# SCH.net
KiCad netlist of a schematic drawn in Altium Designer
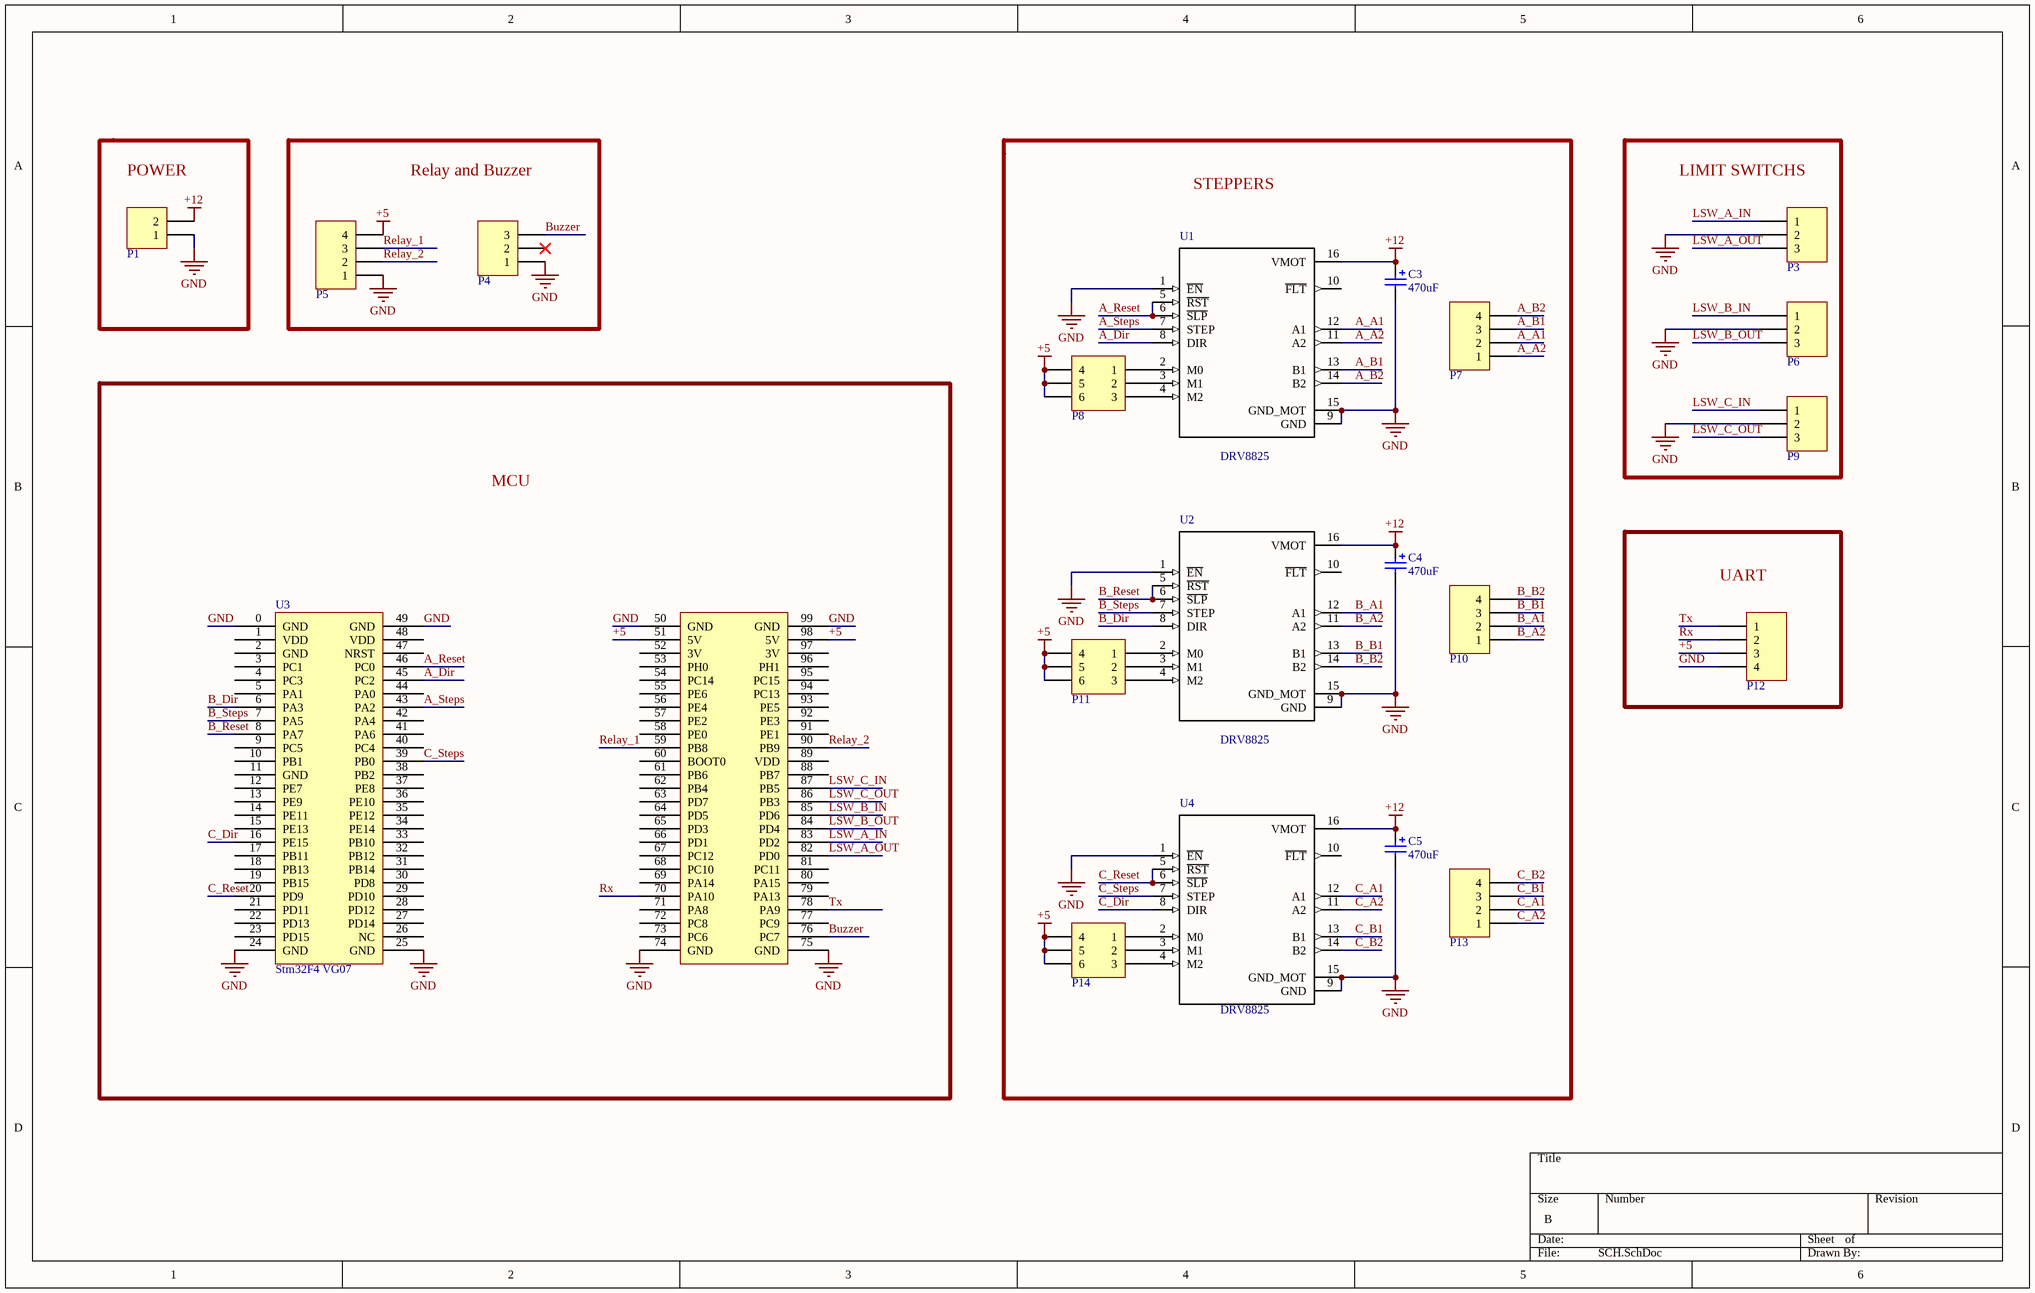
[diagram p0: SCH.SchDoc]

(export (version "E")
  (design (tool "Eeschema 10.0.6"))
  (components
    (comp (ref "C3")
      (value "470uF")
      (footprint "CP1.5/3.4")
      (description "Polarized Capacitor (Radial)")
      (fields (field (name "Comment") "Cap Pol"))
      (libsource (lib "PIF_Library") (part "Cap Pol"))
    )
    (comp (ref "C4")
      (value "470uF")
      (footprint "CP1.5/3.4")
      (description "Polarized Capacitor (Radial)")
      (fields (field (name "Comment") "Cap Pol"))
      (libsource (lib "PIF_Library") (part "Cap Pol"))
    )
    (comp (ref "C5")
      (value "470uF")
      (footprint "CP1.5/3.4")
      (description "Polarized Capacitor (Radial)")
      (fields (field (name "Comment") "Cap Pol"))
      (libsource (lib "PIF_Library") (part "Cap Pol"))
    )
    (comp (ref "P1")
      (value "Domino 2")
      (footprint "DOMINO 2- 5mm")
      (description "Domino, 2-Pin")
      (fields (field (name "PUBLISHER") "Altium Limited"))
      (libsource (lib "PIF_Library") (part "Domino 2"))
    )
    (comp (ref "P3")
      (value "Header 3")
      (footprint "JP3")
      (description "Header, 3-Pin")
      (fields (field (name "PUBLISHER") "Altium Limited"))
      (libsource (lib "PIF_Library") (part "Header 3"))
    )
    (comp (ref "P4")
      (value "Header 3")
      (footprint "JP3")
      (description "Header, 3-Pin")
      (fields (field (name "PUBLISHER") "Altium Limited"))
      (libsource (lib "") (part "Header 3_1"))
    )
    (comp (ref "P5")
      (value "Domino 4")
      (footprint "DOMINO 4 -5mm")
      (description "Domino 4-Pin")
      (fields (field (name "PUBLISHER") "Altium Limited"))
      (libsource (lib "PIF_Library") (part "Domino 4"))
    )
    (comp (ref "P6")
      (value "Header 3")
      (footprint "JP3")
      (description "Header, 3-Pin")
      (fields (field (name "PUBLISHER") "Altium Limited"))
      (libsource (lib "PIF_Library") (part "Header 3"))
    )
    (comp (ref "P7")
      (value "Header 4")
      (footprint "JP4")
      (description "Header, 4-Pin")
      (fields (field (name "PUBLISHER") "Altium Limited"))
      (libsource (lib "") (part "Header 4_1"))
    )
    (comp (ref "P8")
      (value "Header 3X2")
      (footprint "JP3x2")
      (description "Header, 3-Pin, Dual row")
      (fields (field (name "PUBLISHER") "Altium Limited"))
      (libsource (lib "PIF_Library") (part "Header 3X2"))
    )
    (comp (ref "P9")
      (value "Header 3")
      (footprint "JP3")
      (description "Header, 3-Pin")
      (fields (field (name "PUBLISHER") "Altium Limited"))
      (libsource (lib "PIF_Library") (part "Header 3"))
    )
    (comp (ref "P10")
      (value "Header 4")
      (footprint "JP4")
      (description "Header, 4-Pin")
      (fields (field (name "PUBLISHER") "Altium Limited"))
      (libsource (lib "") (part "Header 4_1"))
    )
    (comp (ref "P11")
      (value "Header 3X2")
      (footprint "JP3x2")
      (description "Header, 3-Pin, Dual row")
      (fields (field (name "PUBLISHER") "Altium Limited"))
      (libsource (lib "PIF_Library") (part "Header 3X2"))
    )
    (comp (ref "P12")
      (value "Header 4")
      (footprint "JP4")
      (description "Header, 4-Pin")
      (fields (field (name "PUBLISHER") "Altium Limited"))
      (libsource (lib "PIF_Library") (part "Header 4"))
    )
    (comp (ref "P13")
      (value "Header 4")
      (footprint "JP4")
      (description "Header, 4-Pin")
      (fields (field (name "PUBLISHER") "Altium Limited"))
      (libsource (lib "") (part "Header 4_1"))
    )
    (comp (ref "P14")
      (value "Header 3X2")
      (footprint "JP3x2")
      (description "Header, 3-Pin, Dual row")
      (fields (field (name "PUBLISHER") "Altium Limited"))
      (libsource (lib "PIF_Library") (part "Header 3X2"))
    )
    (comp (ref "U1")
      (value "DRV8825")
      (footprint "*IC_DRV8825_STEPPER_MOTOR_DRIVER_CARRIER")
      (description "DRV8825 Motor Controller/Driver Power Management Evaluation Board")
      (fields (field (name "MP") "DRV8825 STEPPER MOTOR DRIVER CARRIER") (field (name "MF") "Pololu"))
      (libsource (lib "DRV8825_STEPPER_MOTOR_DRIVER_CARRIER") (part "DRV8825_STEPPER_MOTOR_DRIVER_CARRIER"))
    )
    (comp (ref "U2")
      (value "DRV8825")
      (footprint "*IC_DRV8825_STEPPER_MOTOR_DRIVER_CARRIER")
      (description "DRV8825 Motor Controller/Driver Power Management Evaluation Board")
      (fields (field (name "MP") "DRV8825 STEPPER MOTOR DRIVER CARRIER") (field (name "MF") "Pololu"))
      (libsource (lib "DRV8825_STEPPER_MOTOR_DRIVER_CARRIER") (part "DRV8825_STEPPER_MOTOR_DRIVER_CARRIER"))
    )
    (comp (ref "U3")
      (value "Stm32F4 VG07")
      (footprint "stm32f4 hoan chinh")
      (libsource (lib "stm32f4 VG07 hoang loi") (part "STM32F4_VG07 Hoang Loi"))
    )
    (comp (ref "U4")
      (value "DRV8825")
      (footprint "*IC_DRV8825_STEPPER_MOTOR_DRIVER_CARRIER")
      (description "DRV8825 Motor Controller/Driver Power Management Evaluation Board")
      (fields (field (name "MP") "DRV8825 STEPPER MOTOR DRIVER CARRIER") (field (name "MF") "Pololu"))
      (libsource (lib "DRV8825_STEPPER_MOTOR_DRIVER_CARRIER") (part "DRV8825_STEPPER_MOTOR_DRIVER_CARRIER"))
    )
  )
  (nets
    (net (code "1") (name "+5") (class "Default")
      (node (ref "P11") (pin "4") (pinfunction "4_4") (pintype "passive"))
      (node (ref "P11") (pin "5") (pinfunction "5_5") (pintype "passive"))
      (node (ref "P11") (pin "6") (pinfunction "6_6") (pintype "passive"))
      (node (ref "P12") (pin "3") (pinfunction "3_3") (pintype "passive"))
      (node (ref "P14") (pin "4") (pinfunction "4_4") (pintype "passive"))
      (node (ref "P14") (pin "5") (pinfunction "5_5") (pintype "passive"))
      (node (ref "P14") (pin "6") (pinfunction "6_6") (pintype "passive"))
      (node (ref "P5") (pin "4") (pinfunction "4_4") (pintype "passive"))
      (node (ref "P8") (pin "4") (pinfunction "4_4") (pintype "passive"))
      (node (ref "P8") (pin "5") (pinfunction "5_5") (pintype "passive"))
      (node (ref "P8") (pin "6") (pinfunction "6_6") (pintype "passive"))
      (node (ref "U3") (pin "51") (pinfunction "5V_51") (pintype "passive"))
      (node (ref "U3") (pin "98") (pinfunction "5V_98") (pintype "passive"))
    )
    (net (code "2") (name "+12") (class "Default")
      (node (ref "C3") (pin "1") (pinfunction "1_1") (pintype "passive"))
      (node (ref "C4") (pin "1") (pinfunction "1_1") (pintype "passive"))
      (node (ref "C5") (pin "1") (pinfunction "1_1") (pintype "passive"))
      (node (ref "P1") (pin "2") (pinfunction "2_2") (pintype "passive"))
      (node (ref "U1") (pin "16") (pinfunction "VMOT_16") (pintype "power_in"))
      (node (ref "U2") (pin "16") (pinfunction "VMOT_16") (pintype "power_in"))
      (node (ref "U4") (pin "16") (pinfunction "VMOT_16") (pintype "power_in"))
    )
    (net (code "3") (name "/A_A1") (class "Default")
      (node (ref "P7") (pin "2") (pinfunction "2_2") (pintype "passive"))
      (node (ref "U1") (pin "12") (pinfunction "A1_12") (pintype "output"))
    )
    (net (code "4") (name "/A_A2") (class "Default")
      (node (ref "P7") (pin "1") (pinfunction "1_1") (pintype "passive"))
      (node (ref "U1") (pin "11") (pinfunction "A2_11") (pintype "output"))
    )
    (net (code "5") (name "/A_B1") (class "Default")
      (node (ref "P7") (pin "3") (pinfunction "3_3") (pintype "passive"))
      (node (ref "U1") (pin "13") (pinfunction "B1_13") (pintype "output"))
    )
    (net (code "6") (name "/A_B2") (class "Default")
      (node (ref "P7") (pin "4") (pinfunction "4_4") (pintype "passive"))
      (node (ref "U1") (pin "14") (pinfunction "B2_14") (pintype "output"))
    )
    (net (code "7") (name "/A_Dir") (class "Default")
      (node (ref "U1") (pin "8") (pinfunction "DIR_8") (pintype "input"))
      (node (ref "U3") (pin "45") (pinfunction "PC2_45") (pintype "passive"))
    )
    (net (code "8") (name "/A_Reset") (class "Default")
      (node (ref "U1") (pin "5") (pinfunction "~{RST}_5") (pintype "input"))
      (node (ref "U1") (pin "6") (pinfunction "~{SLP}_6") (pintype "input"))
      (node (ref "U3") (pin "46") (pinfunction "PC0_46") (pintype "passive"))
    )
    (net (code "9") (name "/A_Steps") (class "Default")
      (node (ref "U1") (pin "7") (pinfunction "STEP_7") (pintype "input"))
      (node (ref "U3") (pin "43") (pinfunction "PA2_43") (pintype "passive"))
    )
    (net (code "10") (name "/B_A1") (class "Default")
      (node (ref "P10") (pin "2") (pinfunction "2_2") (pintype "passive"))
      (node (ref "U2") (pin "12") (pinfunction "A1_12") (pintype "output"))
    )
    (net (code "11") (name "/B_A2") (class "Default")
      (node (ref "P10") (pin "1") (pinfunction "1_1") (pintype "passive"))
      (node (ref "U2") (pin "11") (pinfunction "A2_11") (pintype "output"))
    )
    (net (code "12") (name "/B_B1") (class "Default")
      (node (ref "P10") (pin "3") (pinfunction "3_3") (pintype "passive"))
      (node (ref "U2") (pin "13") (pinfunction "B1_13") (pintype "output"))
    )
    (net (code "13") (name "/B_B2") (class "Default")
      (node (ref "P10") (pin "4") (pinfunction "4_4") (pintype "passive"))
      (node (ref "U2") (pin "14") (pinfunction "B2_14") (pintype "output"))
    )
    (net (code "14") (name "/B_Dir") (class "Default")
      (node (ref "U2") (pin "8") (pinfunction "DIR_8") (pintype "input"))
      (node (ref "U3") (pin "6") (pinfunction "PA3_6") (pintype "passive"))
    )
    (net (code "15") (name "/B_Reset") (class "Default")
      (node (ref "U2") (pin "5") (pinfunction "~{RST}_5") (pintype "input"))
      (node (ref "U2") (pin "6") (pinfunction "~{SLP}_6") (pintype "input"))
      (node (ref "U3") (pin "8") (pinfunction "PA7_8") (pintype "passive"))
    )
    (net (code "16") (name "/B_Steps") (class "Default")
      (node (ref "U2") (pin "7") (pinfunction "STEP_7") (pintype "input"))
      (node (ref "U3") (pin "7") (pinfunction "PA5_7") (pintype "passive"))
    )
    (net (code "17") (name "/Buzzer") (class "Default")
      (node (ref "P4") (pin "3") (pinfunction "3_3") (pintype "passive"))
      (node (ref "U3") (pin "76") (pinfunction "PC7_76") (pintype "passive"))
    )
    (net (code "18") (name "/C_A1") (class "Default")
      (node (ref "P13") (pin "2") (pinfunction "2_2") (pintype "passive"))
      (node (ref "U4") (pin "12") (pinfunction "A1_12") (pintype "output"))
    )
    (net (code "19") (name "/C_A2") (class "Default")
      (node (ref "P13") (pin "1") (pinfunction "1_1") (pintype "passive"))
      (node (ref "U4") (pin "11") (pinfunction "A2_11") (pintype "output"))
    )
    (net (code "20") (name "/C_B1") (class "Default")
      (node (ref "P13") (pin "3") (pinfunction "3_3") (pintype "passive"))
      (node (ref "U4") (pin "13") (pinfunction "B1_13") (pintype "output"))
    )
    (net (code "21") (name "/C_B2") (class "Default")
      (node (ref "P13") (pin "4") (pinfunction "4_4") (pintype "passive"))
      (node (ref "U4") (pin "14") (pinfunction "B2_14") (pintype "output"))
    )
    (net (code "22") (name "/C_Dir") (class "Default")
      (node (ref "U3") (pin "16") (pinfunction "PE15_16") (pintype "passive"))
      (node (ref "U4") (pin "8") (pinfunction "DIR_8") (pintype "input"))
    )
    (net (code "23") (name "/C_Reset") (class "Default")
      (node (ref "U3") (pin "20") (pinfunction "PD9_20") (pintype "passive"))
      (node (ref "U4") (pin "5") (pinfunction "~{RST}_5") (pintype "input"))
      (node (ref "U4") (pin "6") (pinfunction "~{SLP}_6") (pintype "input"))
    )
    (net (code "24") (name "/C_Steps") (class "Default")
      (node (ref "U3") (pin "39") (pinfunction "PB0_39") (pintype "passive"))
      (node (ref "U4") (pin "7") (pinfunction "STEP_7") (pintype "input"))
    )
    (net (code "25") (name "/LSW_A_IN") (class "Default")
      (node (ref "P3") (pin "1") (pinfunction "1_1") (pintype "passive"))
      (node (ref "U3") (pin "83") (pinfunction "PD2_83") (pintype "passive"))
    )
    (net (code "26") (name "/LSW_A_OUT") (class "Default")
      (node (ref "P3") (pin "3") (pinfunction "3_3") (pintype "passive"))
      (node (ref "U3") (pin "82") (pinfunction "PD0_82") (pintype "passive"))
    )
    (net (code "27") (name "/LSW_B_IN") (class "Default")
      (node (ref "P6") (pin "1") (pinfunction "1_1") (pintype "passive"))
      (node (ref "U3") (pin "85") (pinfunction "PD6_85") (pintype "passive"))
    )
    (net (code "28") (name "/LSW_B_OUT") (class "Default")
      (node (ref "P6") (pin "3") (pinfunction "3_3") (pintype "passive"))
      (node (ref "U3") (pin "84") (pinfunction "PD4_84") (pintype "passive"))
    )
    (net (code "29") (name "/LSW_C_IN") (class "Default")
      (node (ref "P9") (pin "1") (pinfunction "1_1") (pintype "passive"))
      (node (ref "U3") (pin "87") (pinfunction "PB5_87") (pintype "passive"))
    )
    (net (code "30") (name "/LSW_C_OUT") (class "Default")
      (node (ref "P9") (pin "3") (pinfunction "3_3") (pintype "passive"))
      (node (ref "U3") (pin "86") (pinfunction "PB3_86") (pintype "passive"))
    )
    (net (code "31") (name "/Relay_1") (class "Default")
      (node (ref "P5") (pin "3") (pinfunction "3_3") (pintype "passive"))
      (node (ref "U3") (pin "59") (pinfunction "PB8_59") (pintype "passive"))
    )
    (net (code "32") (name "/Relay_2") (class "Default")
      (node (ref "P5") (pin "2") (pinfunction "2_2") (pintype "passive"))
      (node (ref "U3") (pin "90") (pinfunction "PB9_90") (pintype "passive"))
    )
    (net (code "33") (name "/Rx") (class "Default")
      (node (ref "P12") (pin "2") (pinfunction "2_2") (pintype "passive"))
      (node (ref "U3") (pin "70") (pinfunction "PA10_70") (pintype "passive"))
    )
    (net (code "34") (name "/Tx") (class "Default")
      (node (ref "P12") (pin "1") (pinfunction "1_1") (pintype "passive"))
      (node (ref "U3") (pin "78") (pinfunction "PA9_78") (pintype "passive"))
    )
    (net (code "35") (name "GND") (class "Default")
      (node (ref "C3") (pin "2") (pinfunction "2_2") (pintype "passive"))
      (node (ref "C4") (pin "2") (pinfunction "2_2") (pintype "passive"))
      (node (ref "C5") (pin "2") (pinfunction "2_2") (pintype "passive"))
      (node (ref "P1") (pin "1") (pinfunction "1_1") (pintype "passive"))
      (node (ref "P12") (pin "4") (pinfunction "4_4") (pintype "passive"))
      (node (ref "P3") (pin "2") (pinfunction "2_2") (pintype "passive"))
      (node (ref "P4") (pin "1") (pinfunction "1_1") (pintype "passive"))
      (node (ref "P5") (pin "1") (pinfunction "1_1") (pintype "passive"))
      (node (ref "P6") (pin "2") (pinfunction "2_2") (pintype "passive"))
      (node (ref "P9") (pin "2") (pinfunction "2_2") (pintype "passive"))
      (node (ref "U1") (pin "1") (pinfunction "~{EN}_1") (pintype "input"))
      (node (ref "U1") (pin "15") (pinfunction "GND_MOT_15") (pintype "power_in"))
      (node (ref "U1") (pin "9") (pinfunction "GND_9") (pintype "power_in"))
      (node (ref "U2") (pin "1") (pinfunction "~{EN}_1") (pintype "input"))
      (node (ref "U2") (pin "15") (pinfunction "GND_MOT_15") (pintype "power_in"))
      (node (ref "U2") (pin "9") (pinfunction "GND_9") (pintype "power_in"))
      (node (ref "U3") (pin "0") (pinfunction "GND_0") (pintype "passive"))
      (node (ref "U3") (pin "24") (pinfunction "GND_24") (pintype "passive"))
      (node (ref "U3") (pin "25") (pinfunction "GND_25") (pintype "passive"))
      (node (ref "U3") (pin "49") (pinfunction "GND_49") (pintype "passive"))
      (node (ref "U3") (pin "50") (pinfunction "GND_50") (pintype "passive"))
      (node (ref "U3") (pin "74") (pinfunction "GND_74") (pintype "passive"))
      (node (ref "U3") (pin "75") (pinfunction "GND_75") (pintype "passive"))
      (node (ref "U3") (pin "99") (pinfunction "GND_99") (pintype "passive"))
      (node (ref "U4") (pin "1") (pinfunction "~{EN}_1") (pintype "input"))
      (node (ref "U4") (pin "15") (pinfunction "GND_MOT_15") (pintype "power_in"))
      (node (ref "U4") (pin "9") (pinfunction "GND_9") (pintype "power_in"))
    )
    (net (code "36") (name "Net-(U1-M0)") (class "Default")
      (node (ref "P8") (pin "1") (pinfunction "1_1") (pintype "passive"))
      (node (ref "U1") (pin "2") (pinfunction "M0_2") (pintype "input"))
    )
    (net (code "37") (name "Net-(U1-M1)") (class "Default")
      (node (ref "P8") (pin "2") (pinfunction "2_2") (pintype "passive"))
      (node (ref "U1") (pin "3") (pinfunction "M1_3") (pintype "input"))
    )
    (net (code "38") (name "Net-(U1-M2)") (class "Default")
      (node (ref "P8") (pin "3") (pinfunction "3_3") (pintype "passive"))
      (node (ref "U1") (pin "4") (pinfunction "M2_4") (pintype "input"))
    )
    (net (code "39") (name "Net-(U2-M0)") (class "Default")
      (node (ref "P11") (pin "1") (pinfunction "1_1") (pintype "passive"))
      (node (ref "U2") (pin "2") (pinfunction "M0_2") (pintype "input"))
    )
    (net (code "40") (name "Net-(U2-M1)") (class "Default")
      (node (ref "P11") (pin "2") (pinfunction "2_2") (pintype "passive"))
      (node (ref "U2") (pin "3") (pinfunction "M1_3") (pintype "input"))
    )
    (net (code "41") (name "Net-(U2-M2)") (class "Default")
      (node (ref "P11") (pin "3") (pinfunction "3_3") (pintype "passive"))
      (node (ref "U2") (pin "4") (pinfunction "M2_4") (pintype "input"))
    )
    (net (code "42") (name "Net-(U4-M0)") (class "Default")
      (node (ref "P14") (pin "1") (pinfunction "1_1") (pintype "passive"))
      (node (ref "U4") (pin "2") (pinfunction "M0_2") (pintype "input"))
    )
    (net (code "43") (name "Net-(U4-M1)") (class "Default")
      (node (ref "P14") (pin "2") (pinfunction "2_2") (pintype "passive"))
      (node (ref "U4") (pin "3") (pinfunction "M1_3") (pintype "input"))
    )
    (net (code "44") (name "Net-(U4-M2)") (class "Default")
      (node (ref "P14") (pin "3") (pinfunction "3_3") (pintype "passive"))
      (node (ref "U4") (pin "4") (pinfunction "M2_4") (pintype "input"))
    )
    (net (code "45") (name "unconnected-(P4-Pad2)") (class "Default")
      (node (ref "P4") (pin "2") (pinfunction "2_2") (pintype "passive+no_connect"))
    )
    (net (code "46") (name "unconnected-(U1-~{FLT}-Pad10)") (class "Default")
      (node (ref "U1") (pin "10") (pinfunction "~{FLT}_10") (pintype "output"))
    )
    (net (code "47") (name "unconnected-(U2-~{FLT}-Pad10)") (class "Default")
      (node (ref "U2") (pin "10") (pinfunction "~{FLT}_10") (pintype "output"))
    )
    (net (code "48") (name "unconnected-(U3-3V-Pad52)") (class "Default")
      (node (ref "U3") (pin "52") (pinfunction "3V_52") (pintype "passive"))
    )
    (net (code "49") (name "unconnected-(U3-3V-Pad97)") (class "Default")
      (node (ref "U3") (pin "97") (pinfunction "3V_97") (pintype "passive"))
    )
    (net (code "50") (name "unconnected-(U3-BOOT0-Pad60)") (class "Default")
      (node (ref "U3") (pin "60") (pinfunction "BOOT0_60") (pintype "passive"))
    )
    (net (code "51") (name "unconnected-(U3-GND-Pad2)") (class "Default")
      (node (ref "U3") (pin "2") (pinfunction "GND_2") (pintype "passive"))
    )
    (net (code "52") (name "unconnected-(U3-GND-Pad11)") (class "Default")
      (node (ref "U3") (pin "11") (pinfunction "GND_11") (pintype "passive"))
    )
    (net (code "53") (name "unconnected-(U3-NC-Pad26)") (class "Default")
      (node (ref "U3") (pin "26") (pinfunction "NC_26") (pintype "passive"))
    )
    (net (code "54") (name "unconnected-(U3-NRST-Pad47)") (class "Default")
      (node (ref "U3") (pin "47") (pinfunction "NRST_47") (pintype "passive"))
    )
    (net (code "55") (name "unconnected-(U3-PA0-Pad44)") (class "Default")
      (node (ref "U3") (pin "44") (pinfunction "PA0_44") (pintype "passive"))
    )
    (net (code "56") (name "unconnected-(U3-PA1-Pad5)") (class "Default")
      (node (ref "U3") (pin "5") (pinfunction "PA1_5") (pintype "passive"))
    )
    (net (code "57") (name "unconnected-(U3-PA4-Pad42)") (class "Default")
      (node (ref "U3") (pin "42") (pinfunction "PA4_42") (pintype "passive"))
    )
    (net (code "58") (name "unconnected-(U3-PA6-Pad41)") (class "Default")
      (node (ref "U3") (pin "41") (pinfunction "PA6_41") (pintype "passive"))
    )
    (net (code "59") (name "unconnected-(U3-PA8-Pad71)") (class "Default")
      (node (ref "U3") (pin "71") (pinfunction "PA8_71") (pintype "passive"))
    )
    (net (code "60") (name "unconnected-(U3-PA13-Pad79)") (class "Default")
      (node (ref "U3") (pin "79") (pinfunction "PA13_79") (pintype "passive"))
    )
    (net (code "61") (name "unconnected-(U3-PA14-Pad69)") (class "Default")
      (node (ref "U3") (pin "69") (pinfunction "PA14_69") (pintype "passive"))
    )
    (net (code "62") (name "unconnected-(U3-PA15-Pad80)") (class "Default")
      (node (ref "U3") (pin "80") (pinfunction "PA15_80") (pintype "passive"))
    )
    (net (code "63") (name "unconnected-(U3-PB1-Pad10)") (class "Default")
      (node (ref "U3") (pin "10") (pinfunction "PB1_10") (pintype "passive"))
    )
    (net (code "64") (name "unconnected-(U3-PB2-Pad38)") (class "Default")
      (node (ref "U3") (pin "38") (pinfunction "PB2_38") (pintype "passive"))
    )
    (net (code "65") (name "unconnected-(U3-PB4-Pad62)") (class "Default")
      (node (ref "U3") (pin "62") (pinfunction "PB4_62") (pintype "passive"))
    )
    (net (code "66") (name "unconnected-(U3-PB6-Pad61)") (class "Default")
      (node (ref "U3") (pin "61") (pinfunction "PB6_61") (pintype "passive"))
    )
    (net (code "67") (name "unconnected-(U3-PB7-Pad88)") (class "Default")
      (node (ref "U3") (pin "88") (pinfunction "PB7_88") (pintype "passive"))
    )
    (net (code "68") (name "unconnected-(U3-PB10-Pad33)") (class "Default")
      (node (ref "U3") (pin "33") (pinfunction "PB10_33") (pintype "passive"))
    )
    (net (code "69") (name "unconnected-(U3-PB11-Pad17)") (class "Default")
      (node (ref "U3") (pin "17") (pinfunction "PB11_17") (pintype "passive"))
    )
    (net (code "70") (name "unconnected-(U3-PB12-Pad32)") (class "Default")
      (node (ref "U3") (pin "32") (pinfunction "PB12_32") (pintype "passive"))
    )
    (net (code "71") (name "unconnected-(U3-PB13-Pad18)") (class "Default")
      (node (ref "U3") (pin "18") (pinfunction "PB13_18") (pintype "passive"))
    )
    (net (code "72") (name "unconnected-(U3-PB14-Pad31)") (class "Default")
      (node (ref "U3") (pin "31") (pinfunction "PB14_31") (pintype "passive"))
    )
    (net (code "73") (name "unconnected-(U3-PB15-Pad19)") (class "Default")
      (node (ref "U3") (pin "19") (pinfunction "PB15_19") (pintype "passive"))
    )
    (net (code "74") (name "unconnected-(U3-PC1-Pad3)") (class "Default")
      (node (ref "U3") (pin "3") (pinfunction "PC1_3") (pintype "passive"))
    )
    (net (code "75") (name "unconnected-(U3-PC3-Pad4)") (class "Default")
      (node (ref "U3") (pin "4") (pinfunction "PC3_4") (pintype "passive"))
    )
    (net (code "76") (name "unconnected-(U3-PC4-Pad40)") (class "Default")
      (node (ref "U3") (pin "40") (pinfunction "PC4_40") (pintype "passive"))
    )
    (net (code "77") (name "unconnected-(U3-PC5-Pad9)") (class "Default")
      (node (ref "U3") (pin "9") (pinfunction "PC5_9") (pintype "passive"))
    )
    (net (code "78") (name "unconnected-(U3-PC6-Pad73)") (class "Default")
      (node (ref "U3") (pin "73") (pinfunction "PC6_73") (pintype "passive"))
    )
    (net (code "79") (name "unconnected-(U3-PC8-Pad72)") (class "Default")
      (node (ref "U3") (pin "72") (pinfunction "PC8_72") (pintype "passive"))
    )
    (net (code "80") (name "unconnected-(U3-PC9-Pad77)") (class "Default")
      (node (ref "U3") (pin "77") (pinfunction "PC9_77") (pintype "passive"))
    )
    (net (code "81") (name "unconnected-(U3-PC10-Pad68)") (class "Default")
      (node (ref "U3") (pin "68") (pinfunction "PC10_68") (pintype "passive"))
    )
    (net (code "82") (name "unconnected-(U3-PC11-Pad81)") (class "Default")
      (node (ref "U3") (pin "81") (pinfunction "PC11_81") (pintype "passive"))
    )
    (net (code "83") (name "unconnected-(U3-PC12-Pad67)") (class "Default")
      (node (ref "U3") (pin "67") (pinfunction "PC12_67") (pintype "passive"))
    )
    (net (code "84") (name "unconnected-(U3-PC13-Pad94)") (class "Default")
      (node (ref "U3") (pin "94") (pinfunction "PC13_94") (pintype "passive"))
    )
    (net (code "85") (name "unconnected-(U3-PC14-Pad54)") (class "Default")
      (node (ref "U3") (pin "54") (pinfunction "PC14_54") (pintype "passive"))
    )
    (net (code "86") (name "unconnected-(U3-PC15-Pad95)") (class "Default")
      (node (ref "U3") (pin "95") (pinfunction "PC15_95") (pintype "passive"))
    )
    (net (code "87") (name "unconnected-(U3-PD1-Pad66)") (class "Default")
      (node (ref "U3") (pin "66") (pinfunction "PD1_66") (pintype "passive"))
    )
    (net (code "88") (name "unconnected-(U3-PD3-Pad65)") (class "Default")
      (node (ref "U3") (pin "65") (pinfunction "PD3_65") (pintype "passive"))
    )
    (net (code "89") (name "unconnected-(U3-PD5-Pad64)") (class "Default")
      (node (ref "U3") (pin "64") (pinfunction "PD5_64") (pintype "passive"))
    )
    (net (code "90") (name "unconnected-(U3-PD7-Pad63)") (class "Default")
      (node (ref "U3") (pin "63") (pinfunction "PD7_63") (pintype "passive"))
    )
    (net (code "91") (name "unconnected-(U3-PD8-Pad30)") (class "Default")
      (node (ref "U3") (pin "30") (pinfunction "PD8_30") (pintype "passive"))
    )
    (net (code "92") (name "unconnected-(U3-PD10-Pad29)") (class "Default")
      (node (ref "U3") (pin "29") (pinfunction "PD10_29") (pintype "passive"))
    )
    (net (code "93") (name "unconnected-(U3-PD11-Pad21)") (class "Default")
      (node (ref "U3") (pin "21") (pinfunction "PD11_21") (pintype "passive"))
    )
    (net (code "94") (name "unconnected-(U3-PD12-Pad28)") (class "Default")
      (node (ref "U3") (pin "28") (pinfunction "PD12_28") (pintype "passive"))
    )
    (net (code "95") (name "unconnected-(U3-PD13-Pad22)") (class "Default")
      (node (ref "U3") (pin "22") (pinfunction "PD13_22") (pintype "passive"))
    )
    (net (code "96") (name "unconnected-(U3-PD14-Pad27)") (class "Default")
      (node (ref "U3") (pin "27") (pinfunction "PD14_27") (pintype "passive"))
    )
    (net (code "97") (name "unconnected-(U3-PD15-Pad23)") (class "Default")
      (node (ref "U3") (pin "23") (pinfunction "PD15_23") (pintype "passive"))
    )
    (net (code "98") (name "unconnected-(U3-PE0-Pad58)") (class "Default")
      (node (ref "U3") (pin "58") (pinfunction "PE0_58") (pintype "passive"))
    )
    (net (code "99") (name "unconnected-(U3-PE1-Pad91)") (class "Default")
      (node (ref "U3") (pin "91") (pinfunction "PE1_91") (pintype "passive"))
    )
    (net (code "100") (name "unconnected-(U3-PE2-Pad57)") (class "Default")
      (node (ref "U3") (pin "57") (pinfunction "PE2_57") (pintype "passive"))
    )
    (net (code "101") (name "unconnected-(U3-PE3-Pad92)") (class "Default")
      (node (ref "U3") (pin "92") (pinfunction "PE3_92") (pintype "passive"))
    )
    (net (code "102") (name "unconnected-(U3-PE4-Pad56)") (class "Default")
      (node (ref "U3") (pin "56") (pinfunction "PE4_56") (pintype "passive"))
    )
    (net (code "103") (name "unconnected-(U3-PE5-Pad93)") (class "Default")
      (node (ref "U3") (pin "93") (pinfunction "PE5_93") (pintype "passive"))
    )
    (net (code "104") (name "unconnected-(U3-PE6-Pad55)") (class "Default")
      (node (ref "U3") (pin "55") (pinfunction "PE6_55") (pintype "passive"))
    )
    (net (code "105") (name "unconnected-(U3-PE7-Pad12)") (class "Default")
      (node (ref "U3") (pin "12") (pinfunction "PE7_12") (pintype "passive"))
    )
    (net (code "106") (name "unconnected-(U3-PE8-Pad37)") (class "Default")
      (node (ref "U3") (pin "37") (pinfunction "PE8_37") (pintype "passive"))
    )
    (net (code "107") (name "unconnected-(U3-PE9-Pad13)") (class "Default")
      (node (ref "U3") (pin "13") (pinfunction "PE9_13") (pintype "passive"))
    )
    (net (code "108") (name "unconnected-(U3-PE10-Pad36)") (class "Default")
      (node (ref "U3") (pin "36") (pinfunction "PE10_36") (pintype "passive"))
    )
    (net (code "109") (name "unconnected-(U3-PE11-Pad14)") (class "Default")
      (node (ref "U3") (pin "14") (pinfunction "PE11_14") (pintype "passive"))
    )
    (net (code "110") (name "unconnected-(U3-PE12-Pad35)") (class "Default")
      (node (ref "U3") (pin "35") (pinfunction "PE12_35") (pintype "passive"))
    )
    (net (code "111") (name "unconnected-(U3-PE13-Pad15)") (class "Default")
      (node (ref "U3") (pin "15") (pinfunction "PE13_15") (pintype "passive"))
    )
    (net (code "112") (name "unconnected-(U3-PE14-Pad34)") (class "Default")
      (node (ref "U3") (pin "34") (pinfunction "PE14_34") (pintype "passive"))
    )
    (net (code "113") (name "unconnected-(U3-PH0-Pad53)") (class "Default")
      (node (ref "U3") (pin "53") (pinfunction "PH0_53") (pintype "passive"))
    )
    (net (code "114") (name "unconnected-(U3-PH1-Pad96)") (class "Default")
      (node (ref "U3") (pin "96") (pinfunction "PH1_96") (pintype "passive"))
    )
    (net (code "115") (name "unconnected-(U3-VDD-Pad1)") (class "Default")
      (node (ref "U3") (pin "1") (pinfunction "VDD_1") (pintype "passive"))
    )
    (net (code "116") (name "unconnected-(U3-VDD-Pad48)") (class "Default")
      (node (ref "U3") (pin "48") (pinfunction "VDD_48") (pintype "passive"))
    )
    (net (code "117") (name "unconnected-(U3-VDD-Pad89)") (class "Default")
      (node (ref "U3") (pin "89") (pinfunction "VDD_89") (pintype "passive"))
    )
    (net (code "118") (name "unconnected-(U4-~{FLT}-Pad10)") (class "Default")
      (node (ref "U4") (pin "10") (pinfunction "~{FLT}_10") (pintype "output"))
    )
  )
)
